# shankPCB.net
KiCad netlist of a schematic drawn in EasyEDA Pro
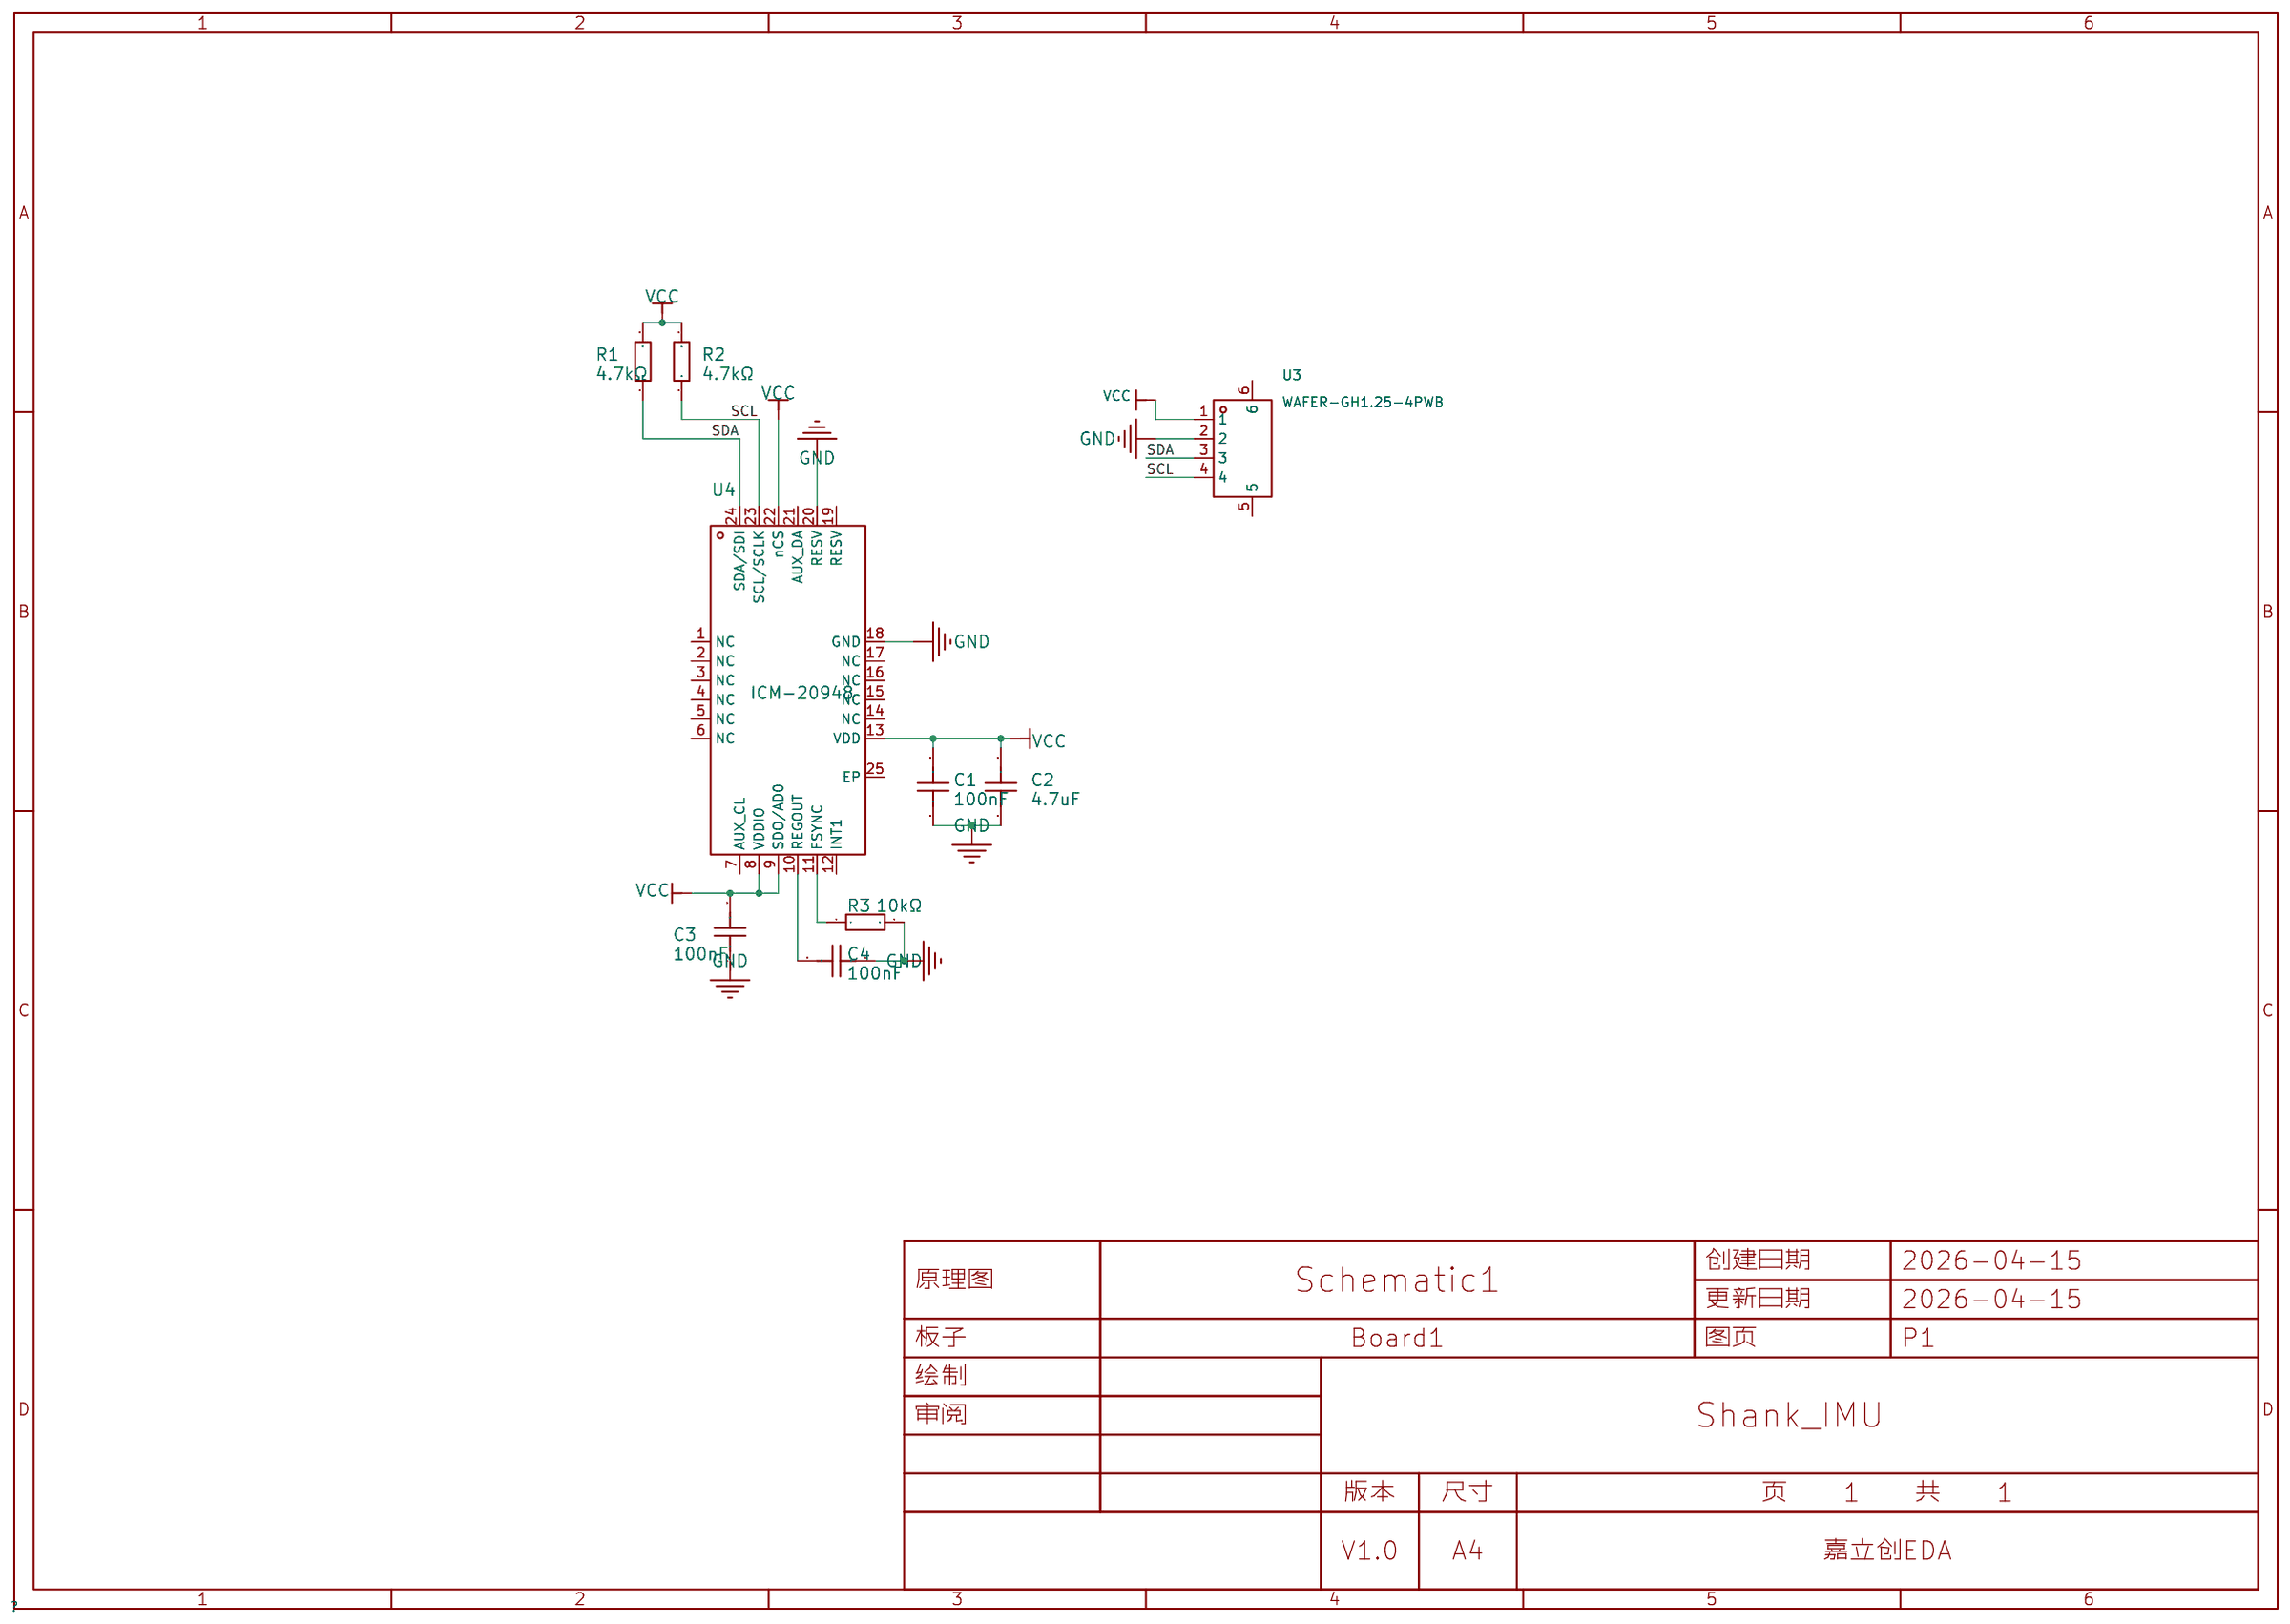
[diagram p0: schematic sheet]

(export (version "E")
  (design (tool "Eeschema 10.0.6"))
  (components
    (comp (ref "C1")
      (value "100nF")
      (fields
        (field (name "Manufacturer Part") "CL05B104KO5NNNC")
        (field (name "Manufacturer") "SAMSUNG(三星)")
      )
      (libsource (lib "easyedapro") (part "Capacitance"))
    )
    (comp (ref "C2")
      (value "4.7uF")
      (description "容值:4.7uF;精度:±20%;额定电压:10V;温度系数:X5R;")
      (fields
        (field (name "Manufacturer Part") "CL05A475MP5NRNC")
        (field (name "Manufacturer") "SAMSUNG(三星)")
      )
      (libsource (lib "easyedapro") (part "Capacitance"))
    )
    (comp (ref "C3")
      (value "100nF")
      (fields
        (field (name "Manufacturer Part") "CL05B104KO5NNNC")
        (field (name "Manufacturer") "SAMSUNG(三星)")
      )
      (libsource (lib "easyedapro") (part "Capacitance"))
    )
    (comp (ref "C4")
      (value "100nF")
      (fields
        (field (name "Manufacturer Part") "CL05B104KO5NNNC")
        (field (name "Manufacturer") "SAMSUNG(三星)")
      )
      (libsource (lib "easyedapro") (part "Capacitance"))
    )
    (comp (ref "R1")
      (value "4.7kΩ")
      (footprint "easyedapro:R0201")
      (description "电阻类型:厚膜电阻;阻值:4.7kΩ;精度:±1%;功率:62.5mW;工作电压:50V;温度系数:±100ppm/℃;")
      (fields
        (field (name "Manufacturer Part") "0402WGF4701TCE")
        (field (name "Manufacturer") "UNI-ROYAL(厚声)")
      )
      (libsource (lib "easyedapro") (part "RC0201FR-0710KL"))
    )
    (comp (ref "R2")
      (value "4.7kΩ")
      (footprint "easyedapro:R0201")
      (description "电阻类型:厚膜电阻;阻值:4.7kΩ;精度:±1%;功率:62.5mW;工作电压:50V;温度系数:±100ppm/℃;")
      (fields
        (field (name "Manufacturer Part") "0402WGF4701TCE")
        (field (name "Manufacturer") "UNI-ROYAL(厚声)")
      )
      (libsource (lib "easyedapro") (part "RC0201FR-0710KL"))
    )
    (comp (ref "R3")
      (value "10kΩ")
      (footprint "easyedapro:R0201")
      (description "电阻类型:厚膜电阻;阻值:10kΩ;精度:±1%;功率:62.5mW;工作电压:50V;温度系数:±100ppm/℃;")
      (fields (field (name "Manufacturer Part") "FRC0402F1002TS") (field (name "Manufacturer") "FOJAN(富捷)"))
      (libsource (lib "easyedapro") (part "RC0201FR-0710KL"))
    )
    (comp (ref "U3")
      (value "WAFER-GH1.25-4PWB")
      (footprint "easyedapro:CONN-SMD_4P-P1.25_XUNPU_WAFER-GH1.25-4PWB")
      (fields (field (name "Manufacturer") "XUNPU(讯普)"))
      (libsource (lib "easyedapro") (part "WAFER-GH1.25-4PWB"))
    )
    (comp (ref "U4")
      (value "ICM-20948")
      (footprint "easyedapro:QFN-24_L3.0-W3.0-P0.40-BL-EP")
      (fields (field (name "Manufacturer") "TDK InvenSense(应美盛)"))
      (libsource (lib "easyedapro") (part "ICM-20948"))
    )
  )
  (nets
    (net (code "1") (name "/SCL") (class "Default")
      (node (ref "R2") (pin "2") (pinfunction "2_2") (pintype "input"))
      (node (ref "U3") (pin "4") (pinfunction "4_4") (pintype "unspecified"))
      (node (ref "U4") (pin "23") (pinfunction "SCL/SCLK_23") (pintype "unspecified"))
    )
    (net (code "2") (name "/SDA") (class "Default")
      (node (ref "R1") (pin "1") (pinfunction "1_1") (pintype "input"))
      (node (ref "U3") (pin "3") (pinfunction "3_3") (pintype "unspecified"))
      (node (ref "U4") (pin "24") (pinfunction "SDA/SDI_24") (pintype "unspecified"))
    )
    (net (code "3") (name "GND") (class "Default")
      (node (ref "C1") (pin "1") (pinfunction "1_1") (pintype "input"))
      (node (ref "C2") (pin "1") (pinfunction "1_1") (pintype "input"))
      (node (ref "C3") (pin "1") (pinfunction "1_1") (pintype "input"))
      (node (ref "C4") (pin "1") (pinfunction "1_1") (pintype "input"))
      (node (ref "R3") (pin "2") (pinfunction "2_2") (pintype "input"))
      (node (ref "U3") (pin "2") (pinfunction "2_2") (pintype "unspecified"))
      (node (ref "U4") (pin "18") (pinfunction "GND_18") (pintype "unspecified"))
      (node (ref "U4") (pin "20") (pinfunction "RESV_20") (pintype "unspecified"))
    )
    (net (code "4") (name "Net-(U4-FSYNC)") (class "Default")
      (node (ref "R3") (pin "1") (pinfunction "1_1") (pintype "input"))
      (node (ref "U4") (pin "11") (pinfunction "FSYNC_11") (pintype "unspecified"))
    )
    (net (code "5") (name "Net-(U4-REGOUT)") (class "Default")
      (node (ref "C4") (pin "2") (pinfunction "2_2") (pintype "input"))
      (node (ref "U4") (pin "10") (pinfunction "REGOUT_10") (pintype "unspecified"))
    )
    (net (code "6") (name "VCC") (class "Default")
      (node (ref "C1") (pin "2") (pinfunction "2_2") (pintype "input"))
      (node (ref "C2") (pin "2") (pinfunction "2_2") (pintype "input"))
      (node (ref "C3") (pin "2") (pinfunction "2_2") (pintype "input"))
      (node (ref "R1") (pin "2") (pinfunction "2_2") (pintype "input"))
      (node (ref "R2") (pin "1") (pinfunction "1_1") (pintype "input"))
      (node (ref "U3") (pin "1") (pinfunction "1_1") (pintype "unspecified"))
      (node (ref "U4") (pin "13") (pinfunction "VDD_13") (pintype "unspecified"))
      (node (ref "U4") (pin "22") (pinfunction "nCS_22") (pintype "unspecified"))
      (node (ref "U4") (pin "8") (pinfunction "VDDIO_8") (pintype "unspecified"))
      (node (ref "U4") (pin "9") (pinfunction "SDO/AD0_9") (pintype "unspecified"))
    )
    (net (code "7") (name "unconnected-(U3-Pad5)") (class "Default")
      (node (ref "U3") (pin "5") (pinfunction "5_5") (pintype "unspecified"))
    )
    (net (code "8") (name "unconnected-(U3-Pad6)") (class "Default")
      (node (ref "U3") (pin "6") (pinfunction "6_6") (pintype "unspecified"))
    )
    (net (code "9") (name "unconnected-(U4-AUX_CL-Pad7)") (class "Default")
      (node (ref "U4") (pin "7") (pinfunction "AUX_CL_7") (pintype "unspecified"))
    )
    (net (code "10") (name "unconnected-(U4-AUX_DA-Pad21)") (class "Default")
      (node (ref "U4") (pin "21") (pinfunction "AUX_DA_21") (pintype "unspecified"))
    )
    (net (code "11") (name "unconnected-(U4-EP-Pad25)") (class "Default")
      (node (ref "U4") (pin "25") (pinfunction "EP_25") (pintype "unspecified"))
    )
    (net (code "12") (name "unconnected-(U4-INT1-Pad12)") (class "Default")
      (node (ref "U4") (pin "12") (pinfunction "INT1_12") (pintype "unspecified"))
    )
    (net (code "13") (name "unconnected-(U4-NC-Pad1)") (class "Default")
      (node (ref "U4") (pin "1") (pinfunction "NC_1") (pintype "unspecified"))
    )
    (net (code "14") (name "unconnected-(U4-NC-Pad2)") (class "Default")
      (node (ref "U4") (pin "2") (pinfunction "NC_2") (pintype "unspecified"))
    )
    (net (code "15") (name "unconnected-(U4-NC-Pad3)") (class "Default")
      (node (ref "U4") (pin "3") (pinfunction "NC_3") (pintype "unspecified"))
    )
    (net (code "16") (name "unconnected-(U4-NC-Pad4)") (class "Default")
      (node (ref "U4") (pin "4") (pinfunction "NC_4") (pintype "unspecified"))
    )
    (net (code "17") (name "unconnected-(U4-NC-Pad5)") (class "Default")
      (node (ref "U4") (pin "5") (pinfunction "NC_5") (pintype "unspecified"))
    )
    (net (code "18") (name "unconnected-(U4-NC-Pad6)") (class "Default")
      (node (ref "U4") (pin "6") (pinfunction "NC_6") (pintype "unspecified"))
    )
    (net (code "19") (name "unconnected-(U4-NC-Pad14)") (class "Default")
      (node (ref "U4") (pin "14") (pinfunction "NC_14") (pintype "unspecified"))
    )
    (net (code "20") (name "unconnected-(U4-NC-Pad15)") (class "Default")
      (node (ref "U4") (pin "15") (pinfunction "NC_15") (pintype "unspecified"))
    )
    (net (code "21") (name "unconnected-(U4-NC-Pad16)") (class "Default")
      (node (ref "U4") (pin "16") (pinfunction "NC_16") (pintype "unspecified"))
    )
    (net (code "22") (name "unconnected-(U4-NC-Pad17)") (class "Default")
      (node (ref "U4") (pin "17") (pinfunction "NC_17") (pintype "unspecified"))
    )
    (net (code "23") (name "unconnected-(U4-RESV-Pad19)") (class "Default")
      (node (ref "U4") (pin "19") (pinfunction "RESV_19") (pintype "unspecified"))
    )
  )
)
